# CB77-EI-Conversion-V1.net
KiCad netlist of a schematic drawn in EAGLE
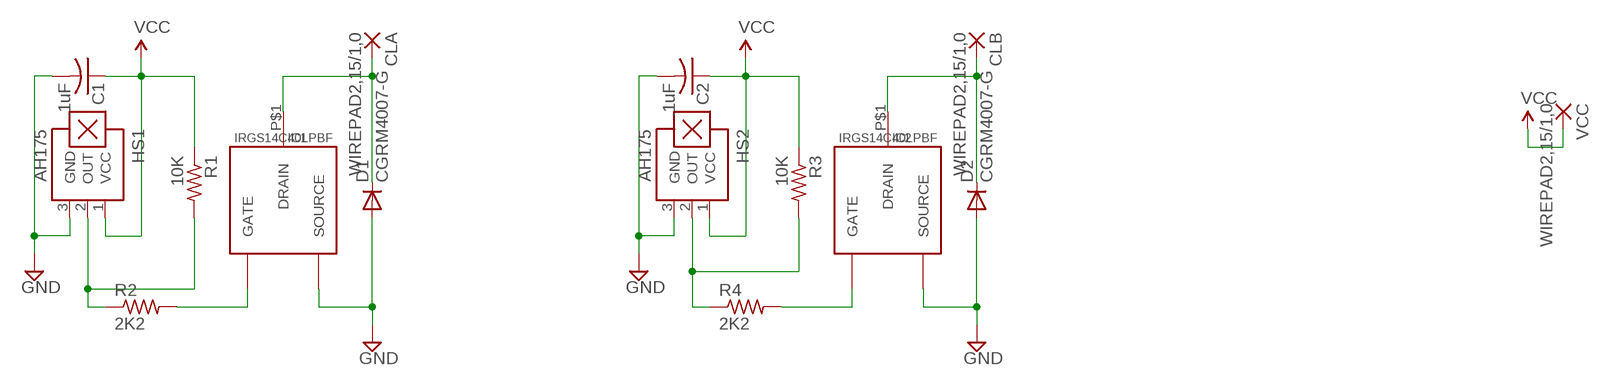
[diagram p0: schematic, sheet 1]

(export (version "E")
  (design (tool "Eeschema 10.0.6"))
  (components
    (comp (ref "C1")
      (value ".1uF")
      (footprint "eagle-import:C0603K")
      (libsource (lib "eagle-import") (part "C-USC0603K"))
    )
    (comp (ref "C2")
      (value ".1uF")
      (footprint "eagle-import:C0603K")
      (libsource (lib "eagle-import") (part "C-USC0603K"))
    )
    (comp (ref "CLA")
      (value "WIREPAD2,15/1,0")
      (footprint "eagle-import:2,15_1,0")
      (libsource (lib "eagle-import") (part "WIREPAD2,15/1,0"))
    )
    (comp (ref "CLB")
      (value "WIREPAD2,15/1,0")
      (footprint "eagle-import:2,15_1,0")
      (libsource (lib "eagle-import") (part "WIREPAD2,15/1,0"))
    )
    (comp (ref "D1")
      (value "CGRM4007-G")
      (footprint "eagle-import:SOD-123_MINI-SMA")
      (libsource (lib "eagle-import") (part "CGRM400-G7"))
    )
    (comp (ref "D2")
      (value "CGRM4007-G")
      (footprint "eagle-import:SOD-123_MINI-SMA")
      (libsource (lib "eagle-import") (part "CGRM400-G7"))
    )
    (comp (ref "HS1")
      (value "AH175")
      (footprint "eagle-import:SOT23-W")
      (fields (field (name "MF") "ALLEGRO MICROSYSTEMS, INC.") (field (name "MPN") "A1301ELHLT-T"))
      (libsource (lib "eagle-import") (part "A13?LH01"))
    )
    (comp (ref "HS2")
      (value "AH175")
      (footprint "eagle-import:SOT23-W")
      (fields (field (name "MF") "ALLEGRO MICROSYSTEMS, INC.") (field (name "MPN") "A1301ELHLT-T"))
      (libsource (lib "eagle-import") (part "A13?LH01"))
    )
    (comp (ref "IC1")
      (value "IRGS14C40LPBF")
      (footprint "eagle-import:TO-263AB")
      (libsource (lib "eagle-import") (part "IRGS14C40LPBF"))
    )
    (comp (ref "IC2")
      (value "IRGS14C40LPBF")
      (footprint "eagle-import:TO-263AB")
      (libsource (lib "eagle-import") (part "IRGS14C40LPBF"))
    )
    (comp (ref "R1")
      (value "10K")
      (footprint "eagle-import:R0603")
      (libsource (lib "eagle-import") (part "R-US_R0603"))
    )
    (comp (ref "R2")
      (value "2K2")
      (footprint "eagle-import:R0603")
      (libsource (lib "eagle-import") (part "R-US_R0603"))
    )
    (comp (ref "R3")
      (value "10K")
      (footprint "eagle-import:R0603")
      (libsource (lib "eagle-import") (part "R-US_R0603"))
    )
    (comp (ref "R4")
      (value "2K2")
      (footprint "eagle-import:R0603")
      (libsource (lib "eagle-import") (part "R-US_R0603"))
    )
    (comp (ref "VCC")
      (value "WIREPAD2,15/1,0")
      (footprint "eagle-import:2,15_1,0")
      (libsource (lib "eagle-import") (part "WIREPAD2,15/1,0"))
    )
  )
  (nets
    (net (code "1") (name "GND") (class "Default")
      (node (ref "C1") (pin "2") (pinfunction "2_2") (pintype "passive"))
      (node (ref "C2") (pin "2") (pinfunction "2_2") (pintype "passive"))
      (node (ref "D1") (pin "A") (pinfunction "A_A") (pintype "passive"))
      (node (ref "D2") (pin "A") (pinfunction "A_A") (pintype "passive"))
      (node (ref "HS1") (pin "3") (pinfunction "GND_3") (pintype "power_in"))
      (node (ref "HS2") (pin "3") (pinfunction "GND_3") (pintype "power_in"))
      (node (ref "IC1") (pin "P$3") (pinfunction "SOURCE_P$3") (pintype "bidirectional"))
      (node (ref "IC2") (pin "P$3") (pinfunction "SOURCE_P$3") (pintype "bidirectional"))
    )
    (net (code "2") (name "Net-(CLA-P)") (class "Default")
      (node (ref "CLA") (pin "1") (pinfunction "P_1") (pintype "passive"))
      (node (ref "D1") (pin "C") (pinfunction "C_C") (pintype "passive"))
      (node (ref "IC1") (pin "P$1") (pinfunction "DRAIN_P$1") (pintype "bidirectional"))
    )
    (net (code "3") (name "Net-(CLB-P)") (class "Default")
      (node (ref "CLB") (pin "1") (pinfunction "P_1") (pintype "passive"))
      (node (ref "D2") (pin "C") (pinfunction "C_C") (pintype "passive"))
      (node (ref "IC2") (pin "P$1") (pinfunction "DRAIN_P$1") (pintype "bidirectional"))
    )
    (net (code "4") (name "Net-(HS1-OUT)") (class "Default")
      (node (ref "HS1") (pin "2") (pinfunction "OUT_2") (pintype "output"))
      (node (ref "R1") (pin "2") (pinfunction "2_2") (pintype "passive"))
      (node (ref "R2") (pin "1") (pinfunction "1_1") (pintype "passive"))
    )
    (net (code "5") (name "Net-(HS2-OUT)") (class "Default")
      (node (ref "HS2") (pin "2") (pinfunction "OUT_2") (pintype "output"))
      (node (ref "R3") (pin "2") (pinfunction "2_2") (pintype "passive"))
      (node (ref "R4") (pin "1") (pinfunction "1_1") (pintype "passive"))
    )
    (net (code "6") (name "Net-(IC1-GATE)") (class "Default")
      (node (ref "IC1") (pin "P$2") (pinfunction "GATE_P$2") (pintype "bidirectional"))
      (node (ref "R2") (pin "2") (pinfunction "2_2") (pintype "passive"))
    )
    (net (code "7") (name "Net-(IC2-GATE)") (class "Default")
      (node (ref "IC2") (pin "P$2") (pinfunction "GATE_P$2") (pintype "bidirectional"))
      (node (ref "R4") (pin "2") (pinfunction "2_2") (pintype "passive"))
    )
    (net (code "8") (name "VCC") (class "Default")
      (node (ref "C1") (pin "1") (pinfunction "1_1") (pintype "passive"))
      (node (ref "C2") (pin "1") (pinfunction "1_1") (pintype "passive"))
      (node (ref "HS1") (pin "1") (pinfunction "VCC_1") (pintype "power_in"))
      (node (ref "HS2") (pin "1") (pinfunction "VCC_1") (pintype "power_in"))
      (node (ref "R1") (pin "1") (pinfunction "1_1") (pintype "passive"))
      (node (ref "R3") (pin "1") (pinfunction "1_1") (pintype "passive"))
      (node (ref "VCC") (pin "1") (pinfunction "P_1") (pintype "passive"))
    )
  )
)
